# Boost_Buck.net
KiCad netlist of a schematic drawn in Altium Designer
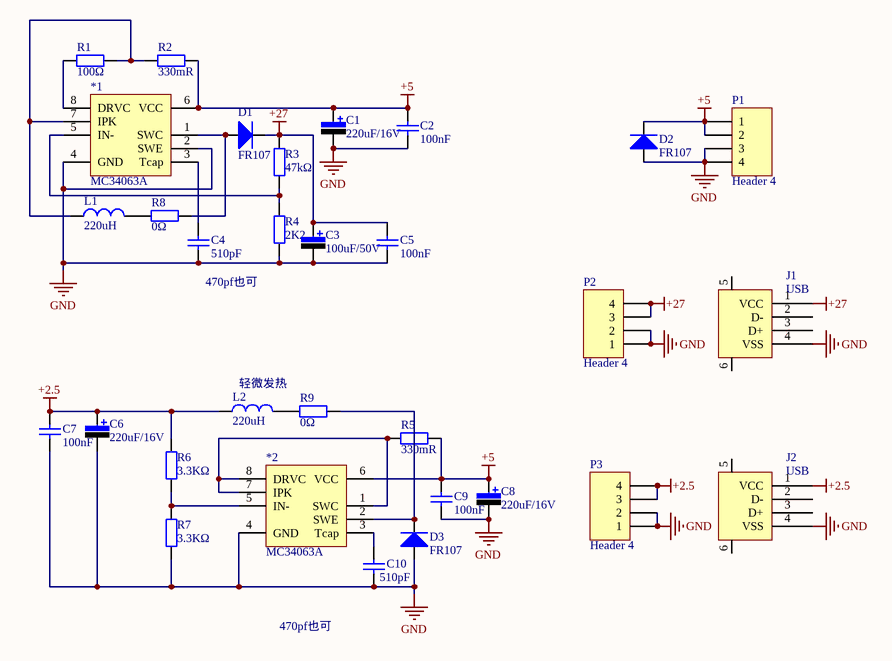
[diagram p0: Boost&Buck.SchDoc]

(export (version "E")
  (design (tool "Eeschema 10.0.6"))
  (components
    (comp (ref "*1") (value "MC34063A") (footprint "SOP-8") (libsource (lib "fszhang") (part "MC34063A")))
    (comp (ref "*2") (value "MC34063A") (footprint "SOP-8") (libsource (lib "fszhang") (part "MC34063A")))
    (comp (ref "C1")
      (value "220uF/16V")
      (footprint "C-RB-S6")
      (description "极性电解电容")
      (fields (field (name "PUBLISHER") "Altium Limited"))
      (libsource (lib "fszhang") (part "Cap Pol"))
    )
    (comp (ref "C2")
      (value "100nF")
      (footprint "0805_C")
      (description "贴片电容")
      (libsource (lib "Miscellaneous Devices LC") (part "0805 100nF(104) 10% 50V"))
    )
    (comp (ref "C3")
      (value "100uF/50V")
      (footprint "C-RB-S8")
      (description "极性电解电容")
      (fields (field (name "PUBLISHER") "Altium Limited"))
      (libsource (lib "fszhang") (part "Cap Pol"))
    )
    (comp (ref "C4")
      (value "510pF")
      (footprint "0805_C")
      (description "贴片电容")
      (libsource (lib "Miscellaneous Devices LC") (part "0805 470pF (471) 10% 50V"))
    )
    (comp (ref "C5")
      (value "100nF")
      (footprint "0805_C")
      (description "贴片电容")
      (libsource (lib "Miscellaneous Devices LC") (part "0805 100nF(104) 10% 50V"))
    )
    (comp (ref "C6")
      (value "220uF/16V")
      (footprint "C-RB-S6")
      (description "极性电解电容")
      (fields (field (name "PUBLISHER") "Altium Limited"))
      (libsource (lib "fszhang") (part "Cap Pol"))
    )
    (comp (ref "C7")
      (value "100nF")
      (footprint "0805_C")
      (description "贴片电容")
      (libsource (lib "Miscellaneous Devices LC") (part "0805 100nF(104) 10% 50V"))
    )
    (comp (ref "C8")
      (value "220uF/16V")
      (footprint "C-RB-S6")
      (description "极性电解电容")
      (fields (field (name "PUBLISHER") "Altium Limited"))
      (libsource (lib "fszhang") (part "Cap Pol"))
    )
    (comp (ref "C9")
      (value "100nF")
      (footprint "0805_C")
      (description "贴片电容")
      (libsource (lib "Miscellaneous Devices LC") (part "0805 100nF(104) 10% 50V"))
    )
    (comp (ref "C10")
      (value "510pF")
      (footprint "0805_C")
      (description "贴片电容")
      (libsource (lib "Miscellaneous Devices LC") (part "0805 470pF (471) 10% 50V"))
    )
    (comp (ref "D1")
      (value "FR107")
      (footprint "DIODE-SMA")
      (description "二极管")
      (fields (field (name "PUBLISHER") "Altium Limited"))
      (libsource (lib "fszhang") (part "Diode"))
    )
    (comp (ref "D2")
      (value "FR107")
      (footprint "DIODE-SMA")
      (description "二极管")
      (fields (field (name "PUBLISHER") "Altium Limited"))
      (libsource (lib "fszhang") (part "Diode"))
    )
    (comp (ref "D3")
      (value "FR107")
      (footprint "DIODE-SMA")
      (description "二极管")
      (fields (field (name "PUBLISHER") "Altium Limited"))
      (libsource (lib "fszhang") (part "Diode"))
    )
    (comp (ref "J1")
      (value "USB")
      (footprint "USB_A1")
      (description "USB接口")
      (libsource (lib "fszhang") (part "USB"))
    )
    (comp (ref "J2")
      (value "USB")
      (footprint "USB_A1")
      (description "USB接口")
      (libsource (lib "fszhang") (part "USB"))
    )
    (comp (ref "L1")
      (value "220uH")
      (footprint "CDRH104R")
      (description "电感")
      (fields (field (name "PUBLISHER") "Altium Limited"))
      (libsource (lib "fszhang") (part "Inductor"))
    )
    (comp (ref "L2")
      (value "220uH")
      (footprint "CDRH104R")
      (description "电感")
      (fields (field (name "PUBLISHER") "Altium Limited"))
      (libsource (lib "fszhang") (part "Inductor"))
    )
    (comp (ref "P1")
      (value "Header 4")
      (footprint "HDR1X4")
      (description "Header, 4-Pin")
      (fields (field (name "PUBLISHER") "Altium Limited"))
      (libsource (lib "") (part "Header 4_1"))
    )
    (comp (ref "P2")
      (value "Header 4")
      (footprint "HDR1X4")
      (description "Header, 4-Pin")
      (fields (field (name "PUBLISHER") "Altium Limited"))
      (libsource (lib "Miscellaneous Connectors") (part "Header 4"))
    )
    (comp (ref "P3")
      (value "Header 4")
      (footprint "HDR1X4")
      (description "Header, 4-Pin")
      (fields (field (name "PUBLISHER") "Altium Limited"))
      (libsource (lib "Miscellaneous Connectors") (part "Header 4"))
    )
    (comp (ref "R1")
      (value "100Ω")
      (footprint "0805_R")
      (description "贴片电阻")
      (libsource (lib "Miscellaneous Devices LC") (part "0805 100Ω (1000) 1%"))
    )
    (comp (ref "R2")
      (value "330mR")
      (footprint "1206_R")
      (description "贴片电阻")
      (libsource (lib "Miscellaneous Devices LC") (part "1206 0.1Ω (R100) 1%"))
    )
    (comp (ref "R3")
      (value "47kΩ")
      (footprint "0805_R")
      (description "贴片电阻")
      (libsource (lib "") (part "0805 100Ω (1000) 1%_1"))
    )
    (comp (ref "R4")
      (value "2K2")
      (footprint "0805_R")
      (description "贴片电阻")
      (libsource (lib "") (part "0805 100Ω (1000) 1%_1"))
    )
    (comp (ref "R5")
      (value "330mR")
      (footprint "1206_R")
      (description "贴片电阻")
      (libsource (lib "Miscellaneous Devices LC") (part "1206 0.1Ω (R100) 1%"))
    )
    (comp (ref "R6")
      (value "3.3KΩ")
      (footprint "0805_R")
      (description "贴片电阻")
      (libsource (lib "Miscellaneous Devices LC") (part "0805 3.3KΩ (3301) 1%"))
    )
    (comp (ref "R7")
      (value "3.3KΩ")
      (footprint "0805_R")
      (description "贴片电阻")
      (libsource (lib "Miscellaneous Devices LC") (part "0805 3.3KΩ (3301) 1%"))
    )
    (comp (ref "R8")
      (value "0Ω")
      (footprint "0805_R")
      (description "贴片电阻")
      (libsource (lib "Miscellaneous Devices LC") (part "0805 0Ω (0R0) 1%"))
    )
    (comp (ref "R9")
      (value "0Ω")
      (footprint "0805_R")
      (description "贴片电阻")
      (libsource (lib "Miscellaneous Devices LC") (part "0805 0Ω (0R0) 1%"))
    )
  )
  (nets
    (net (code "1") (name "+2.5") (class "Default")
      (node (ref "C6") (pin "1") (pinfunction "1_1") (pintype "passive"))
      (node (ref "C7") (pin "1") (pinfunction "1_1") (pintype "passive"))
      (node (ref "J2") (pin "1") (pinfunction "VCC_1") (pintype "passive"))
      (node (ref "L2") (pin "1") (pinfunction "1_1") (pintype "passive"))
      (node (ref "P3") (pin "3") (pinfunction "3_3") (pintype "passive"))
      (node (ref "P3") (pin "4") (pinfunction "4_4") (pintype "passive"))
      (node (ref "R6") (pin "2") (pinfunction "2_2") (pintype "passive"))
    )
    (net (code "2") (name "+5") (class "Default")
      (node (ref "*1") (pin "6") (pinfunction "VCC_6") (pintype "passive"))
      (node (ref "*2") (pin "6") (pinfunction "VCC_6") (pintype "passive"))
      (node (ref "C1") (pin "1") (pinfunction "1_1") (pintype "passive"))
      (node (ref "C2") (pin "1") (pinfunction "1_1") (pintype "passive"))
      (node (ref "C8") (pin "1") (pinfunction "1_1") (pintype "passive"))
      (node (ref "C9") (pin "1") (pinfunction "1_1") (pintype "passive"))
      (node (ref "D2") (pin "2") (pinfunction "K_2") (pintype "passive"))
      (node (ref "P1") (pin "1") (pinfunction "1_1") (pintype "passive"))
      (node (ref "P1") (pin "2") (pinfunction "2_2") (pintype "passive"))
      (node (ref "R2") (pin "2") (pinfunction "2_2") (pintype "passive"))
      (node (ref "R5") (pin "2") (pinfunction "2_2") (pintype "passive"))
    )
    (net (code "3") (name "+27") (class "Default")
      (node (ref "C3") (pin "1") (pinfunction "1_1") (pintype "passive"))
      (node (ref "C5") (pin "1") (pinfunction "1_1") (pintype "passive"))
      (node (ref "D1") (pin "2") (pinfunction "K_2") (pintype "passive"))
      (node (ref "J1") (pin "1") (pinfunction "VCC_1") (pintype "passive"))
      (node (ref "P2") (pin "3") (pinfunction "3_3") (pintype "passive"))
      (node (ref "P2") (pin "4") (pinfunction "4_4") (pintype "passive"))
      (node (ref "R3") (pin "2") (pinfunction "2_2") (pintype "passive"))
    )
    (net (code "4") (name "GND") (class "Default")
      (node (ref "*1") (pin "2") (pinfunction "SWE_2") (pintype "passive"))
      (node (ref "*1") (pin "4") (pinfunction "GND_4") (pintype "passive"))
      (node (ref "*2") (pin "4") (pinfunction "GND_4") (pintype "passive"))
      (node (ref "C1") (pin "2") (pinfunction "2_2") (pintype "passive"))
      (node (ref "C10") (pin "1") (pinfunction "1_1") (pintype "passive"))
      (node (ref "C2") (pin "2") (pinfunction "2_2") (pintype "passive"))
      (node (ref "C3") (pin "2") (pinfunction "2_2") (pintype "passive"))
      (node (ref "C4") (pin "1") (pinfunction "1_1") (pintype "passive"))
      (node (ref "C5") (pin "2") (pinfunction "2_2") (pintype "passive"))
      (node (ref "C6") (pin "2") (pinfunction "2_2") (pintype "passive"))
      (node (ref "C7") (pin "2") (pinfunction "2_2") (pintype "passive"))
      (node (ref "C8") (pin "2") (pinfunction "2_2") (pintype "passive"))
      (node (ref "C9") (pin "2") (pinfunction "2_2") (pintype "passive"))
      (node (ref "D2") (pin "1") (pinfunction "A_1") (pintype "passive"))
      (node (ref "D3") (pin "1") (pinfunction "A_1") (pintype "passive"))
      (node (ref "J1") (pin "4") (pinfunction "VSS_4") (pintype "passive"))
      (node (ref "J2") (pin "4") (pinfunction "VSS_4") (pintype "passive"))
      (node (ref "P1") (pin "3") (pinfunction "3_3") (pintype "passive"))
      (node (ref "P1") (pin "4") (pinfunction "4_4") (pintype "passive"))
      (node (ref "P2") (pin "1") (pinfunction "1_1") (pintype "passive"))
      (node (ref "P2") (pin "2") (pinfunction "2_2") (pintype "passive"))
      (node (ref "P3") (pin "1") (pinfunction "1_1") (pintype "passive"))
      (node (ref "P3") (pin "2") (pinfunction "2_2") (pintype "passive"))
      (node (ref "R4") (pin "1") (pinfunction "1_1") (pintype "passive"))
      (node (ref "R7") (pin "1") (pinfunction "1_1") (pintype "passive"))
    )
    (net (code "5") (name "Net-(*1-DRVC)") (class "Default")
      (node (ref "*1") (pin "8") (pinfunction "DRVC_8") (pintype "passive"))
      (node (ref "R1") (pin "1") (pinfunction "1_1") (pintype "passive"))
    )
    (net (code "6") (name "Net-(*1-IN-)") (class "Default")
      (node (ref "*1") (pin "5") (pinfunction "IN-_5") (pintype "passive"))
      (node (ref "R3") (pin "1") (pinfunction "1_1") (pintype "passive"))
      (node (ref "R4") (pin "2") (pinfunction "2_2") (pintype "passive"))
    )
    (net (code "7") (name "Net-(*1-IPK)") (class "Default")
      (node (ref "*1") (pin "7") (pinfunction "IPK_7") (pintype "passive"))
      (node (ref "L1") (pin "1") (pinfunction "1_1") (pintype "passive"))
      (node (ref "R1") (pin "2") (pinfunction "2_2") (pintype "passive"))
      (node (ref "R2") (pin "1") (pinfunction "1_1") (pintype "passive"))
    )
    (net (code "8") (name "Net-(*1-SWC)") (class "Default")
      (node (ref "*1") (pin "1") (pinfunction "SWC_1") (pintype "passive"))
      (node (ref "D1") (pin "1") (pinfunction "A_1") (pintype "passive"))
      (node (ref "R8") (pin "2") (pinfunction "2_2") (pintype "passive"))
    )
    (net (code "9") (name "Net-(*1-Tcap)") (class "Default")
      (node (ref "*1") (pin "3") (pinfunction "Tcap_3") (pintype "passive"))
      (node (ref "C4") (pin "2") (pinfunction "2_2") (pintype "passive"))
    )
    (net (code "10") (name "Net-(*2-DRVC)") (class "Default")
      (node (ref "*2") (pin "1") (pinfunction "SWC_1") (pintype "passive"))
      (node (ref "*2") (pin "7") (pinfunction "IPK_7") (pintype "passive"))
      (node (ref "*2") (pin "8") (pinfunction "DRVC_8") (pintype "passive"))
      (node (ref "R5") (pin "1") (pinfunction "1_1") (pintype "passive"))
    )
    (net (code "11") (name "Net-(*2-IN-)") (class "Default")
      (node (ref "*2") (pin "5") (pinfunction "IN-_5") (pintype "passive"))
      (node (ref "R6") (pin "1") (pinfunction "1_1") (pintype "passive"))
      (node (ref "R7") (pin "2") (pinfunction "2_2") (pintype "passive"))
    )
    (net (code "12") (name "Net-(*2-SWE)") (class "Default")
      (node (ref "*2") (pin "2") (pinfunction "SWE_2") (pintype "passive"))
      (node (ref "D3") (pin "2") (pinfunction "K_2") (pintype "passive"))
      (node (ref "R9") (pin "2") (pinfunction "2_2") (pintype "passive"))
    )
    (net (code "13") (name "Net-(*2-Tcap)") (class "Default")
      (node (ref "*2") (pin "3") (pinfunction "Tcap_3") (pintype "passive"))
      (node (ref "C10") (pin "2") (pinfunction "2_2") (pintype "passive"))
    )
    (net (code "14") (name "Net-(L1-Pad2)") (class "Default")
      (node (ref "L1") (pin "2") (pinfunction "2_2") (pintype "passive"))
      (node (ref "R8") (pin "1") (pinfunction "1_1") (pintype "passive"))
    )
    (net (code "15") (name "Net-(L2-Pad2)") (class "Default")
      (node (ref "L2") (pin "2") (pinfunction "2_2") (pintype "passive"))
      (node (ref "R9") (pin "1") (pinfunction "1_1") (pintype "passive"))
    )
    (net (code "16") (name "unconnected-(J1-D+-Pad3)") (class "Default")
      (node (ref "J1") (pin "3") (pinfunction "D+_3") (pintype "passive"))
    )
    (net (code "17") (name "unconnected-(J1-D--Pad2)") (class "Default")
      (node (ref "J1") (pin "2") (pinfunction "D-_2") (pintype "passive"))
    )
    (net (code "18") (name "unconnected-(J1-Pad5)") (class "Default")
      (node (ref "J1") (pin "5") (pinfunction "5_5") (pintype "passive"))
    )
    (net (code "19") (name "unconnected-(J1-Pad6)") (class "Default")
      (node (ref "J1") (pin "6") (pinfunction "6_6") (pintype "passive"))
    )
    (net (code "20") (name "unconnected-(J2-D+-Pad3)") (class "Default")
      (node (ref "J2") (pin "3") (pinfunction "D+_3") (pintype "passive"))
    )
    (net (code "21") (name "unconnected-(J2-D--Pad2)") (class "Default")
      (node (ref "J2") (pin "2") (pinfunction "D-_2") (pintype "passive"))
    )
    (net (code "22") (name "unconnected-(J2-Pad5)") (class "Default")
      (node (ref "J2") (pin "5") (pinfunction "5_5") (pintype "passive"))
    )
    (net (code "23") (name "unconnected-(J2-Pad6)") (class "Default")
      (node (ref "J2") (pin "6") (pinfunction "6_6") (pintype "passive"))
    )
  )
)
